# Conn_B.net
KiCad netlist of a schematic drawn in Altium Designer
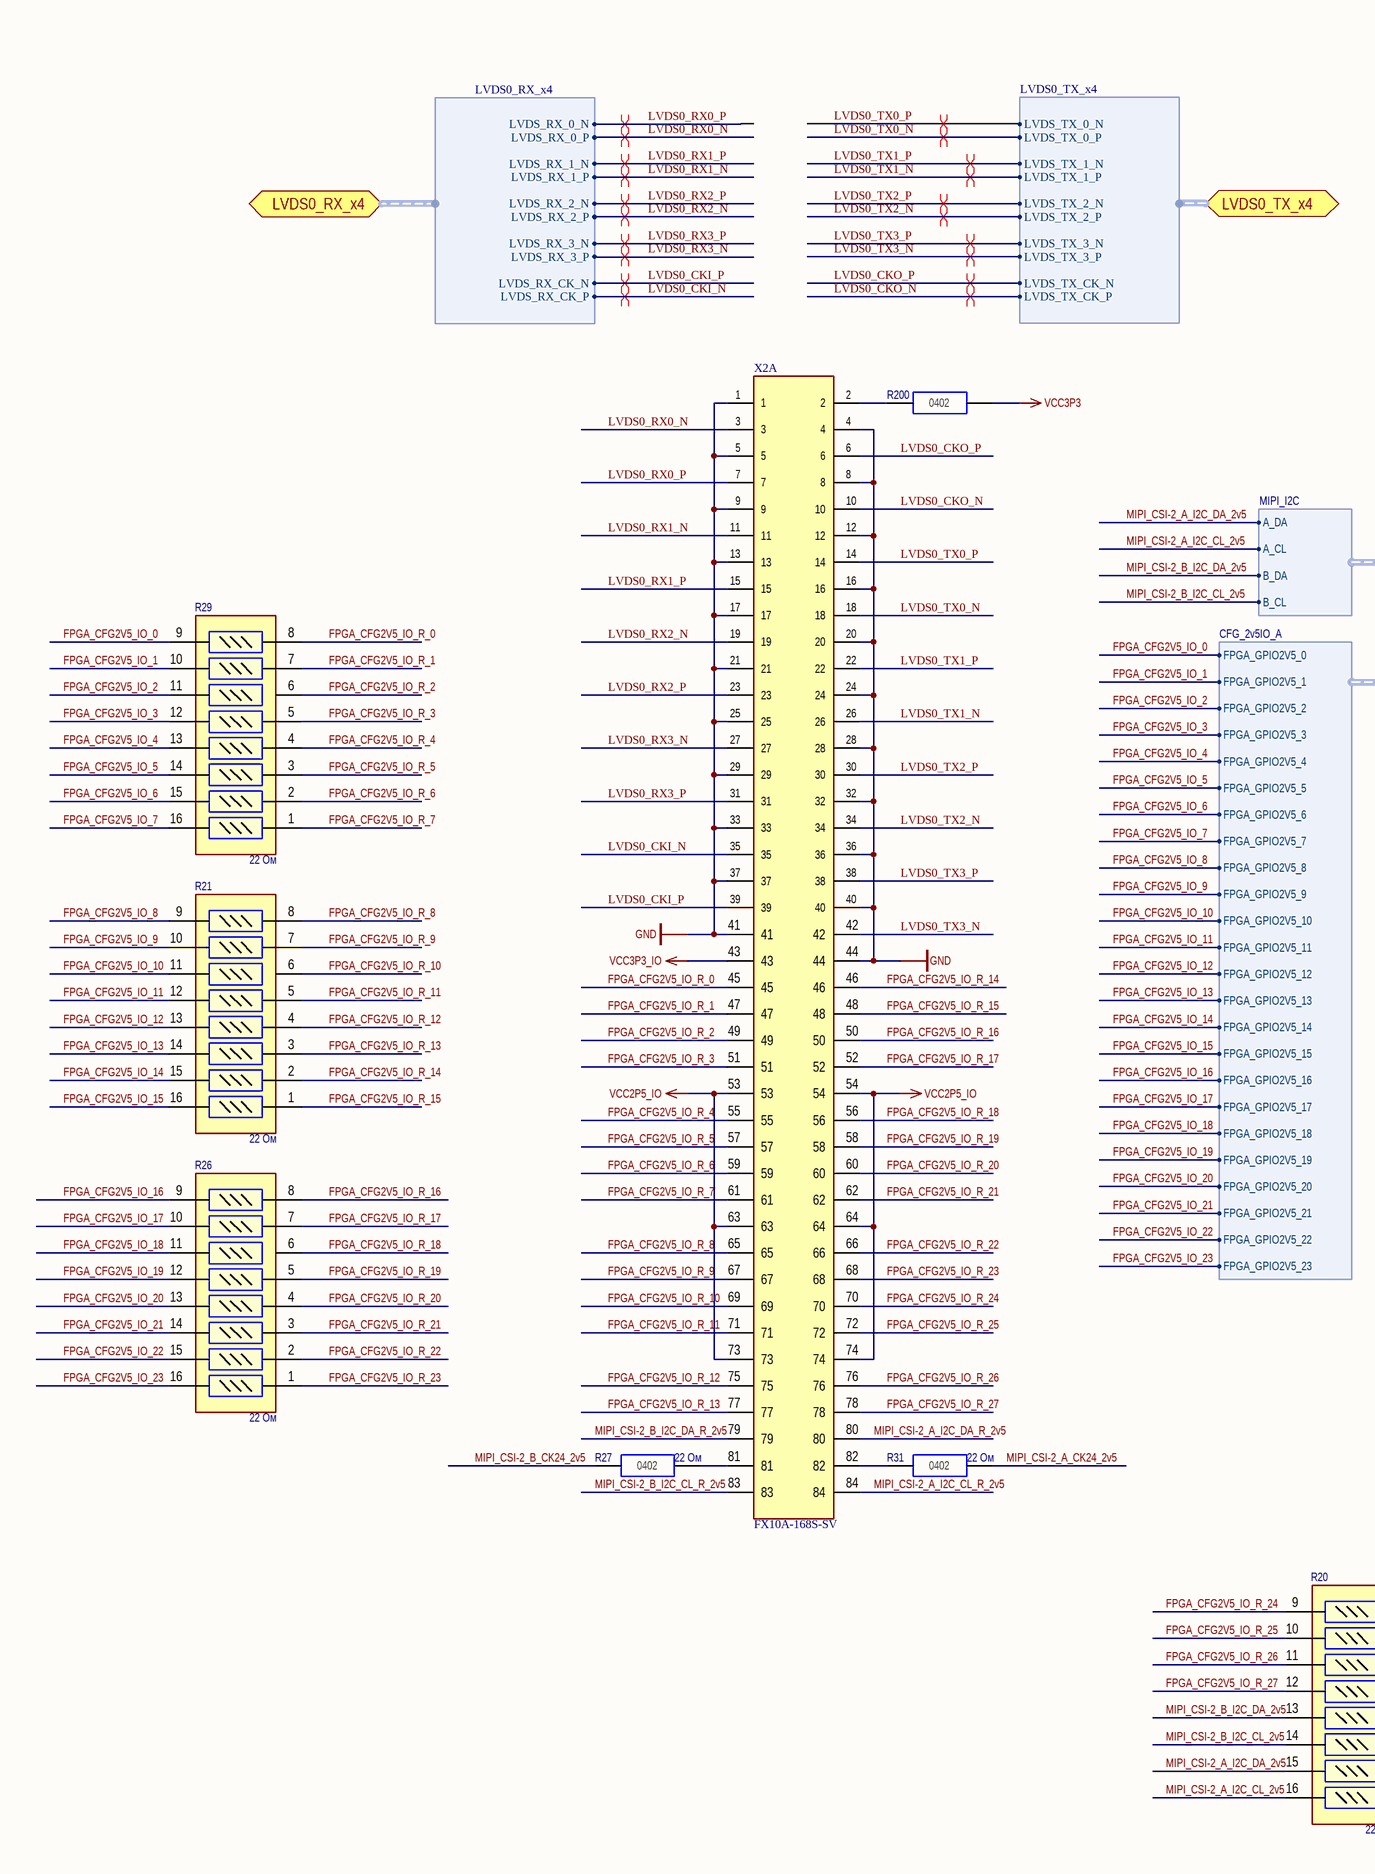
[diagram p0: Conn_B.SchDoc, left]
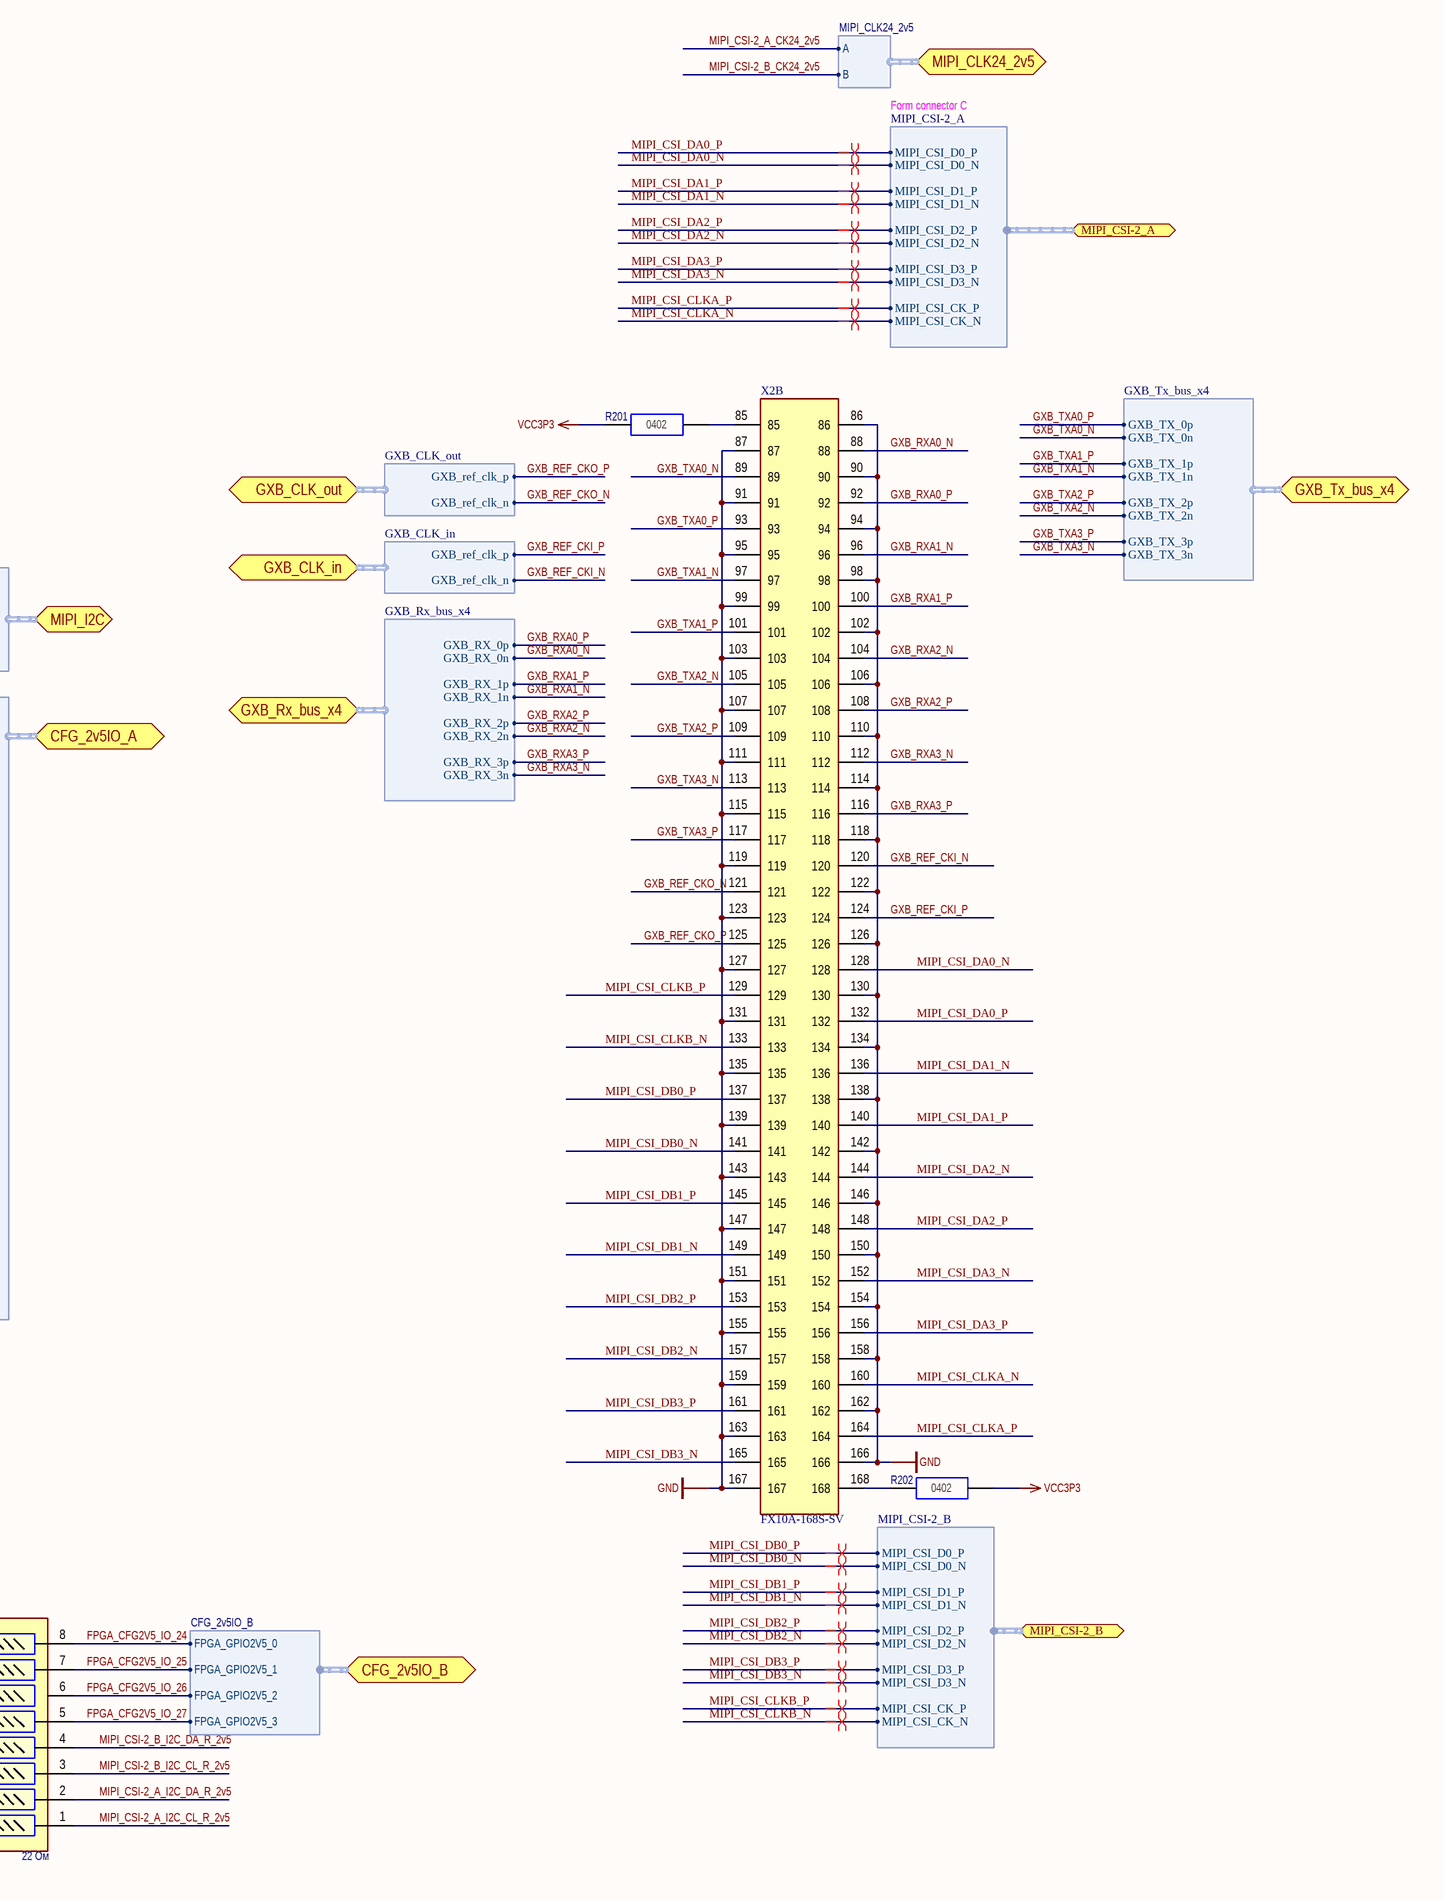
[diagram p1: Conn_B.SchDoc, right]

(export (version "E")
  (design (tool "Eeschema 10.0.6"))
  (components
    (comp (ref "R20")
      (value "22 Ом")
      (footprint "CAT16-J8")
      (description "Набор чип резисторов")
      (fields (field (name "Comment") "YC248-JR-07-22 Ом"))
      (libsource (lib "SD_IC") (part "YC248-JR-07-#"))
    )
    (comp (ref "R21")
      (value "22 Ом")
      (footprint "CAT16-J8")
      (description "Набор чип резисторов")
      (fields (field (name "Comment") "YC248-JR-07-22 Ом"))
      (libsource (lib "SD_IC") (part "YC248-JR-07-#"))
    )
    (comp (ref "R26")
      (value "22 Ом")
      (footprint "CAT16-J8")
      (description "Набор чип резисторов")
      (fields (field (name "Comment") "YC248-JR-07-22 Ом"))
      (libsource (lib "SD_IC") (part "YC248-JR-07-#"))
    )
    (comp (ref "R27")
      (value "22 Ом")
      (footprint "CR0402(1005)")
      (description "Чип резистор")
      (fields (field (name "TOLERANCE") "5%") (field (name "Comment") "CR0402-22 Ом-±5%"))
      (libsource (lib "Чип резисторы") (part "CR0402-#-±5%"))
    )
    (comp (ref "R29")
      (value "22 Ом")
      (footprint "CAT16-J8")
      (description "Набор чип резисторов")
      (fields (field (name "Comment") "YC248-JR-07-22 Ом"))
      (libsource (lib "SD_IC") (part "YC248-JR-07-#"))
    )
    (comp (ref "R31")
      (value "22 Ом")
      (footprint "CR0402(1005)")
      (description "Чип резистор")
      (fields (field (name "TOLERANCE") "5%") (field (name "Comment") "CR0402-22 Ом-±5%"))
      (libsource (lib "Чип резисторы") (part "CR0402-#-±5%"))
    )
    (comp (ref "R200")
      (value "CR0402-0 Ом-±5%")
      (footprint "CR0402(1005)")
      (description "Чип резистор")
      (fields (field (name "TOLERANCE") "5%"))
      (libsource (lib "Резисторы") (part "CR0402-#-±5%"))
    )
    (comp (ref "R201")
      (value "CR0402-0 Ом-±5%")
      (footprint "CR0402(1005)")
      (description "Чип резистор")
      (fields (field (name "TOLERANCE") "5%"))
      (libsource (lib "Резисторы") (part "CR0402-#-±5%"))
    )
    (comp (ref "R202")
      (value "CR0402-0 Ом-±5%")
      (footprint "CR0402(1005)")
      (description "Чип резистор")
      (fields (field (name "TOLERANCE") "5%"))
      (libsource (lib "Резисторы") (part "CR0402-#-±5%"))
    )
    (comp (ref "X2")
      (value "FX10A-168S-SV")
      (footprint "FX10A-168S-SV")
      (libsource (lib "SD_IC") (part "FX10A-168S-SV"))
    )
  )
  (nets
    (net (code "13") (name "/FPGA_CFG2V5_IO_0") (class "Default")
      (node (ref "R29") (pin "9") (pintype "passive"))
    )
    (net (code "14") (name "/FPGA_CFG2V5_IO_1") (class "Default")
      (node (ref "R29") (pin "10") (pintype "passive"))
    )
    (net (code "15") (name "/FPGA_CFG2V5_IO_2") (class "Default")
      (node (ref "R29") (pin "11") (pintype "passive"))
    )
    (net (code "16") (name "/FPGA_CFG2V5_IO_3") (class "Default")
      (node (ref "R29") (pin "12") (pintype "passive"))
    )
    (net (code "17") (name "/FPGA_CFG2V5_IO_4") (class "Default")
      (node (ref "R29") (pin "13") (pintype "passive"))
    )
    (net (code "18") (name "/FPGA_CFG2V5_IO_5") (class "Default")
      (node (ref "R29") (pin "14") (pintype "passive"))
    )
    (net (code "19") (name "/FPGA_CFG2V5_IO_6") (class "Default")
      (node (ref "R29") (pin "15") (pintype "passive"))
    )
    (net (code "20") (name "/FPGA_CFG2V5_IO_7") (class "Default")
      (node (ref "R29") (pin "16") (pintype "passive"))
    )
    (net (code "21") (name "/FPGA_CFG2V5_IO_8") (class "Default")
      (node (ref "R21") (pin "9") (pintype "passive"))
    )
    (net (code "22") (name "/FPGA_CFG2V5_IO_9") (class "Default")
      (node (ref "R21") (pin "10") (pintype "passive"))
    )
    (net (code "23") (name "/FPGA_CFG2V5_IO_10") (class "Default")
      (node (ref "R21") (pin "11") (pintype "passive"))
    )
    (net (code "24") (name "/FPGA_CFG2V5_IO_11") (class "Default")
      (node (ref "R21") (pin "12") (pintype "passive"))
    )
    (net (code "25") (name "/FPGA_CFG2V5_IO_12") (class "Default")
      (node (ref "R21") (pin "13") (pintype "passive"))
    )
    (net (code "26") (name "/FPGA_CFG2V5_IO_13") (class "Default")
      (node (ref "R21") (pin "14") (pintype "passive"))
    )
    (net (code "27") (name "/FPGA_CFG2V5_IO_14") (class "Default")
      (node (ref "R21") (pin "15") (pintype "passive"))
    )
    (net (code "28") (name "/FPGA_CFG2V5_IO_15") (class "Default")
      (node (ref "R21") (pin "16") (pintype "passive"))
    )
    (net (code "29") (name "/FPGA_CFG2V5_IO_16") (class "Default")
      (node (ref "R26") (pin "9") (pintype "passive"))
    )
    (net (code "30") (name "/FPGA_CFG2V5_IO_17") (class "Default")
      (node (ref "R26") (pin "10") (pintype "passive"))
    )
    (net (code "31") (name "/FPGA_CFG2V5_IO_18") (class "Default")
      (node (ref "R26") (pin "11") (pintype "passive"))
    )
    (net (code "32") (name "/FPGA_CFG2V5_IO_19") (class "Default")
      (node (ref "R26") (pin "12") (pintype "passive"))
    )
    (net (code "33") (name "/FPGA_CFG2V5_IO_20") (class "Default")
      (node (ref "R26") (pin "13") (pintype "passive"))
    )
    (net (code "34") (name "/FPGA_CFG2V5_IO_21") (class "Default")
      (node (ref "R26") (pin "14") (pintype "passive"))
    )
    (net (code "35") (name "/FPGA_CFG2V5_IO_22") (class "Default")
      (node (ref "R26") (pin "15") (pintype "passive"))
    )
    (net (code "36") (name "/FPGA_CFG2V5_IO_23") (class "Default")
      (node (ref "R26") (pin "16") (pintype "passive"))
    )
    (net (code "37") (name "/FPGA_CFG2V5_IO_24") (class "Default")
      (node (ref "R20") (pin "8") (pintype "passive"))
    )
    (net (code "38") (name "/FPGA_CFG2V5_IO_25") (class "Default")
      (node (ref "R20") (pin "7") (pintype "passive"))
    )
    (net (code "39") (name "/FPGA_CFG2V5_IO_26") (class "Default")
      (node (ref "R20") (pin "6") (pintype "passive"))
    )
    (net (code "40") (name "/FPGA_CFG2V5_IO_27") (class "Default")
      (node (ref "R20") (pin "5") (pintype "passive"))
    )
    (net (code "41") (name "/FPGA_CFG2V5_IO_R_0") (class "Default")
      (node (ref "R29") (pin "8") (pintype "passive"))
      (node (ref "X2") (pin "45") (pinfunction "45_45") (pintype "passive"))
    )
    (net (code "42") (name "/FPGA_CFG2V5_IO_R_1") (class "Default")
      (node (ref "R29") (pin "7") (pintype "passive"))
      (node (ref "X2") (pin "47") (pinfunction "47_47") (pintype "passive"))
    )
    (net (code "43") (name "/FPGA_CFG2V5_IO_R_2") (class "Default")
      (node (ref "R29") (pin "6") (pintype "passive"))
      (node (ref "X2") (pin "49") (pinfunction "49_49") (pintype "passive"))
    )
    (net (code "44") (name "/FPGA_CFG2V5_IO_R_3") (class "Default")
      (node (ref "R29") (pin "5") (pintype "passive"))
      (node (ref "X2") (pin "51") (pinfunction "51_51") (pintype "passive"))
    )
    (net (code "45") (name "/FPGA_CFG2V5_IO_R_4") (class "Default")
      (node (ref "R29") (pin "4") (pintype "passive"))
      (node (ref "X2") (pin "55") (pinfunction "55_55") (pintype "passive"))
    )
    (net (code "46") (name "/FPGA_CFG2V5_IO_R_5") (class "Default")
      (node (ref "R29") (pin "3") (pintype "passive"))
      (node (ref "X2") (pin "57") (pinfunction "57_57") (pintype "passive"))
    )
    (net (code "47") (name "/FPGA_CFG2V5_IO_R_6") (class "Default")
      (node (ref "R29") (pin "2") (pintype "passive"))
      (node (ref "X2") (pin "59") (pinfunction "59_59") (pintype "passive"))
    )
    (net (code "48") (name "/FPGA_CFG2V5_IO_R_7") (class "Default")
      (node (ref "R29") (pin "1") (pintype "passive"))
      (node (ref "X2") (pin "61") (pinfunction "61_61") (pintype "passive"))
    )
    (net (code "49") (name "/FPGA_CFG2V5_IO_R_8") (class "Default")
      (node (ref "R21") (pin "8") (pintype "passive"))
      (node (ref "X2") (pin "65") (pinfunction "65_65") (pintype "passive"))
    )
    (net (code "50") (name "/FPGA_CFG2V5_IO_R_9") (class "Default")
      (node (ref "R21") (pin "7") (pintype "passive"))
      (node (ref "X2") (pin "67") (pinfunction "67_67") (pintype "passive"))
    )
    (net (code "51") (name "/FPGA_CFG2V5_IO_R_10") (class "Default")
      (node (ref "R21") (pin "6") (pintype "passive"))
      (node (ref "X2") (pin "69") (pinfunction "69_69") (pintype "passive"))
    )
    (net (code "52") (name "/FPGA_CFG2V5_IO_R_11") (class "Default")
      (node (ref "R21") (pin "5") (pintype "passive"))
      (node (ref "X2") (pin "71") (pinfunction "71_71") (pintype "passive"))
    )
    (net (code "53") (name "/FPGA_CFG2V5_IO_R_12") (class "Default")
      (node (ref "R21") (pin "4") (pintype "passive"))
      (node (ref "X2") (pin "75") (pinfunction "75_75") (pintype "passive"))
    )
    (net (code "54") (name "/FPGA_CFG2V5_IO_R_13") (class "Default")
      (node (ref "R21") (pin "3") (pintype "passive"))
      (node (ref "X2") (pin "77") (pinfunction "77_77") (pintype "passive"))
    )
    (net (code "55") (name "/FPGA_CFG2V5_IO_R_14") (class "Default")
      (node (ref "R21") (pin "2") (pintype "passive"))
      (node (ref "X2") (pin "46") (pinfunction "46_46") (pintype "passive"))
    )
    (net (code "56") (name "/FPGA_CFG2V5_IO_R_15") (class "Default")
      (node (ref "R21") (pin "1") (pintype "passive"))
      (node (ref "X2") (pin "48") (pinfunction "48_48") (pintype "passive"))
    )
    (net (code "57") (name "/FPGA_CFG2V5_IO_R_16") (class "Default")
      (node (ref "R26") (pin "8") (pintype "passive"))
      (node (ref "X2") (pin "50") (pinfunction "50_50") (pintype "passive"))
    )
    (net (code "58") (name "/FPGA_CFG2V5_IO_R_17") (class "Default")
      (node (ref "R26") (pin "7") (pintype "passive"))
      (node (ref "X2") (pin "52") (pinfunction "52_52") (pintype "passive"))
    )
    (net (code "59") (name "/FPGA_CFG2V5_IO_R_18") (class "Default")
      (node (ref "R26") (pin "6") (pintype "passive"))
      (node (ref "X2") (pin "56") (pinfunction "56_56") (pintype "passive"))
    )
    (net (code "60") (name "/FPGA_CFG2V5_IO_R_19") (class "Default")
      (node (ref "R26") (pin "5") (pintype "passive"))
      (node (ref "X2") (pin "58") (pinfunction "58_58") (pintype "passive"))
    )
    (net (code "61") (name "/FPGA_CFG2V5_IO_R_20") (class "Default")
      (node (ref "R26") (pin "4") (pintype "passive"))
      (node (ref "X2") (pin "60") (pinfunction "60_60") (pintype "passive"))
    )
    (net (code "62") (name "/FPGA_CFG2V5_IO_R_21") (class "Default")
      (node (ref "R26") (pin "3") (pintype "passive"))
      (node (ref "X2") (pin "62") (pinfunction "62_62") (pintype "passive"))
    )
    (net (code "63") (name "/FPGA_CFG2V5_IO_R_22") (class "Default")
      (node (ref "R26") (pin "2") (pintype "passive"))
      (node (ref "X2") (pin "66") (pinfunction "66_66") (pintype "passive"))
    )
    (net (code "64") (name "/FPGA_CFG2V5_IO_R_23") (class "Default")
      (node (ref "R26") (pin "1") (pintype "passive"))
      (node (ref "X2") (pin "68") (pinfunction "68_68") (pintype "passive"))
    )
    (net (code "65") (name "/FPGA_CFG2V5_IO_R_24") (class "Default")
      (node (ref "R20") (pin "9") (pintype "passive"))
      (node (ref "X2") (pin "70") (pinfunction "70_70") (pintype "passive"))
    )
    (net (code "66") (name "/FPGA_CFG2V5_IO_R_25") (class "Default")
      (node (ref "R20") (pin "10") (pintype "passive"))
      (node (ref "X2") (pin "72") (pinfunction "72_72") (pintype "passive"))
    )
    (net (code "67") (name "/FPGA_CFG2V5_IO_R_26") (class "Default")
      (node (ref "R20") (pin "11") (pintype "passive"))
      (node (ref "X2") (pin "76") (pinfunction "76_76") (pintype "passive"))
    )
    (net (code "68") (name "/FPGA_CFG2V5_IO_R_27") (class "Default")
      (node (ref "R20") (pin "12") (pintype "passive"))
      (node (ref "X2") (pin "78") (pinfunction "78_78") (pintype "passive"))
    )
    (net (code "69") (name "/GXB_REF_CKI_N") (class "Default")
      (node (ref "X2") (pin "120") (pinfunction "120_120") (pintype "passive"))
    )
    (net (code "70") (name "/GXB_REF_CKI_P") (class "Default")
      (node (ref "X2") (pin "124") (pinfunction "124_124") (pintype "passive"))
    )
    (net (code "71") (name "/GXB_REF_CKO_N") (class "Default")
      (node (ref "X2") (pin "121") (pinfunction "121_121") (pintype "passive"))
    )
    (net (code "72") (name "/GXB_REF_CKO_P") (class "Default")
      (node (ref "X2") (pin "125") (pinfunction "125_125") (pintype "passive"))
    )
    (net (code "73") (name "/GXB_RXA0_N") (class "Default")
      (node (ref "X2") (pin "88") (pinfunction "88_88") (pintype "passive"))
    )
    (net (code "74") (name "/GXB_RXA0_P") (class "Default")
      (node (ref "X2") (pin "92") (pinfunction "92_92") (pintype "passive"))
    )
    (net (code "75") (name "/GXB_RXA1_N") (class "Default")
      (node (ref "X2") (pin "96") (pinfunction "96_96") (pintype "passive"))
    )
    (net (code "76") (name "/GXB_RXA1_P") (class "Default")
      (node (ref "X2") (pin "100") (pinfunction "100_100") (pintype "passive"))
    )
    (net (code "77") (name "/GXB_RXA2_N") (class "Default")
      (node (ref "X2") (pin "104") (pinfunction "104_104") (pintype "passive"))
    )
    (net (code "78") (name "/GXB_RXA2_P") (class "Default")
      (node (ref "X2") (pin "108") (pinfunction "108_108") (pintype "passive"))
    )
    (net (code "79") (name "/GXB_RXA3_N") (class "Default")
      (node (ref "X2") (pin "112") (pinfunction "112_112") (pintype "passive"))
    )
    (net (code "80") (name "/GXB_RXA3_P") (class "Default")
      (node (ref "X2") (pin "116") (pinfunction "116_116") (pintype "passive"))
    )
    (net (code "81") (name "/GXB_TXA0_N") (class "Default")
      (node (ref "X2") (pin "89") (pinfunction "89_89") (pintype "passive"))
    )
    (net (code "82") (name "/GXB_TXA0_P") (class "Default")
      (node (ref "X2") (pin "93") (pinfunction "93_93") (pintype "passive"))
    )
    (net (code "83") (name "/GXB_TXA1_N") (class "Default")
      (node (ref "X2") (pin "97") (pinfunction "97_97") (pintype "passive"))
    )
    (net (code "84") (name "/GXB_TXA1_P") (class "Default")
      (node (ref "X2") (pin "101") (pinfunction "101_101") (pintype "passive"))
    )
    (net (code "85") (name "/GXB_TXA2_N") (class "Default")
      (node (ref "X2") (pin "105") (pinfunction "105_105") (pintype "passive"))
    )
    (net (code "86") (name "/GXB_TXA2_P") (class "Default")
      (node (ref "X2") (pin "109") (pinfunction "109_109") (pintype "passive"))
    )
    (net (code "87") (name "/GXB_TXA3_N") (class "Default")
      (node (ref "X2") (pin "113") (pinfunction "113_113") (pintype "passive"))
    )
    (net (code "88") (name "/GXB_TXA3_P") (class "Default")
      (node (ref "X2") (pin "117") (pinfunction "117_117") (pintype "passive"))
    )
    (net (code "89") (name "/LVDS0_CKI_N") (class "Default")
      (node (ref "X2") (pin "35") (pinfunction "35_35") (pintype "passive"))
    )
    (net (code "90") (name "/LVDS0_CKI_P") (class "Default")
      (node (ref "X2") (pin "39") (pinfunction "39_39") (pintype "passive"))
    )
    (net (code "91") (name "/LVDS0_CKO_N") (class "Default")
      (node (ref "X2") (pin "10") (pinfunction "10_10") (pintype "passive"))
    )
    (net (code "92") (name "/LVDS0_CKO_P") (class "Default")
      (node (ref "X2") (pin "6") (pinfunction "6_6") (pintype "passive"))
    )
    (net (code "93") (name "/LVDS0_RX0_N") (class "Default")
      (node (ref "X2") (pin "3") (pinfunction "3_3") (pintype "passive"))
    )
    (net (code "94") (name "/LVDS0_RX0_P") (class "Default")
      (node (ref "X2") (pin "7") (pinfunction "7_7") (pintype "passive"))
    )
    (net (code "95") (name "/LVDS0_RX1_N") (class "Default")
      (node (ref "X2") (pin "11") (pinfunction "11_11") (pintype "passive"))
    )
    (net (code "96") (name "/LVDS0_RX1_P") (class "Default")
      (node (ref "X2") (pin "15") (pinfunction "15_15") (pintype "passive"))
    )
    (net (code "97") (name "/LVDS0_RX2_N") (class "Default")
      (node (ref "X2") (pin "19") (pinfunction "19_19") (pintype "passive"))
    )
    (net (code "98") (name "/LVDS0_RX2_P") (class "Default")
      (node (ref "X2") (pin "23") (pinfunction "23_23") (pintype "passive"))
    )
    (net (code "99") (name "/LVDS0_RX3_N") (class "Default")
      (node (ref "X2") (pin "27") (pinfunction "27_27") (pintype "passive"))
    )
    (net (code "100") (name "/LVDS0_RX3_P") (class "Default")
      (node (ref "X2") (pin "31") (pinfunction "31_31") (pintype "passive"))
    )
    (net (code "101") (name "/LVDS0_TX0_N") (class "Default")
      (node (ref "X2") (pin "18") (pinfunction "18_18") (pintype "passive"))
    )
    (net (code "102") (name "/LVDS0_TX0_P") (class "Default")
      (node (ref "X2") (pin "14") (pinfunction "14_14") (pintype "passive"))
    )
    (net (code "103") (name "/LVDS0_TX1_N") (class "Default")
      (node (ref "X2") (pin "26") (pinfunction "26_26") (pintype "passive"))
    )
    (net (code "104") (name "/LVDS0_TX1_P") (class "Default")
      (node (ref "X2") (pin "22") (pinfunction "22_22") (pintype "passive"))
    )
    (net (code "105") (name "/LVDS0_TX2_N") (class "Default")
      (node (ref "X2") (pin "34") (pinfunction "34_34") (pintype "passive"))
    )
    (net (code "106") (name "/LVDS0_TX2_P") (class "Default")
      (node (ref "X2") (pin "30") (pinfunction "30_30") (pintype "passive"))
    )
    (net (code "107") (name "/LVDS0_TX3_N") (class "Default")
      (node (ref "X2") (pin "42") (pinfunction "42_42") (pintype "passive"))
    )
    (net (code "108") (name "/LVDS0_TX3_P") (class "Default")
      (node (ref "X2") (pin "38") (pinfunction "38_38") (pintype "passive"))
    )
    (net (code "109") (name "/MIPI_CSI-2_A_CK24_2v5") (class "Default")
      (node (ref "R31") (pin "2") (pinfunction "-_2") (pintype "passive"))
    )
    (net (code "110") (name "/MIPI_CSI-2_A_I2C_CL_2v5") (class "Default")
      (node (ref "R20") (pin "16") (pintype "passive"))
    )
    (net (code "111") (name "/MIPI_CSI-2_A_I2C_CL_R_2v5") (class "Default")
      (node (ref "R20") (pin "1") (pintype "passive"))
      (node (ref "X2") (pin "84") (pinfunction "84_84") (pintype "passive"))
    )
    (net (code "112") (name "/MIPI_CSI-2_A_I2C_DA_2v5") (class "Default")
      (node (ref "R20") (pin "15") (pintype "passive"))
    )
    (net (code "113") (name "/MIPI_CSI-2_A_I2C_DA_R_2v5") (class "Default")
      (node (ref "R20") (pin "2") (pintype "passive"))
      (node (ref "X2") (pin "80") (pinfunction "80_80") (pintype "passive"))
    )
    (net (code "114") (name "/MIPI_CSI-2_B_CK24_2v5") (class "Default")
      (node (ref "R27") (pin "1") (pinfunction "+_1") (pintype "passive"))
    )
    (net (code "115") (name "/MIPI_CSI-2_B_I2C_CL_2v5") (class "Default")
      (node (ref "R20") (pin "14") (pintype "passive"))
    )
    (net (code "116") (name "/MIPI_CSI-2_B_I2C_CL_R_2v5") (class "Default")
      (node (ref "R20") (pin "3") (pintype "passive"))
      (node (ref "X2") (pin "83") (pinfunction "83_83") (pintype "passive"))
    )
    (net (code "117") (name "/MIPI_CSI-2_B_I2C_DA_2v5") (class "Default")
      (node (ref "R20") (pin "13") (pintype "passive"))
    )
    (net (code "118") (name "/MIPI_CSI-2_B_I2C_DA_R_2v5") (class "Default")
      (node (ref "R20") (pin "4") (pintype "passive"))
      (node (ref "X2") (pin "79") (pinfunction "79_79") (pintype "passive"))
    )
    (net (code "119") (name "/MIPI_CSI_CLKA_N") (class "Default")
      (node (ref "X2") (pin "160") (pinfunction "160_160") (pintype "passive"))
    )
    (net (code "120") (name "/MIPI_CSI_CLKA_P") (class "Default")
      (node (ref "X2") (pin "164") (pinfunction "164_164") (pintype "passive"))
    )
    (net (code "121") (name "/MIPI_CSI_CLKB_N") (class "Default")
      (node (ref "X2") (pin "133") (pinfunction "133_133") (pintype "passive"))
    )
    (net (code "122") (name "/MIPI_CSI_CLKB_P") (class "Default")
      (node (ref "X2") (pin "129") (pinfunction "129_129") (pintype "passive"))
    )
    (net (code "123") (name "/MIPI_CSI_DA0_N") (class "Default")
      (node (ref "X2") (pin "128") (pinfunction "128_128") (pintype "passive"))
    )
    (net (code "124") (name "/MIPI_CSI_DA0_P") (class "Default")
      (node (ref "X2") (pin "132") (pinfunction "132_132") (pintype "passive"))
    )
    (net (code "125") (name "/MIPI_CSI_DA1_N") (class "Default")
      (node (ref "X2") (pin "136") (pinfunction "136_136") (pintype "passive"))
    )
    (net (code "126") (name "/MIPI_CSI_DA1_P") (class "Default")
      (node (ref "X2") (pin "140") (pinfunction "140_140") (pintype "passive"))
    )
    (net (code "127") (name "/MIPI_CSI_DA2_N") (class "Default")
      (node (ref "X2") (pin "144") (pinfunction "144_144") (pintype "passive"))
    )
    (net (code "128") (name "/MIPI_CSI_DA2_P") (class "Default")
      (node (ref "X2") (pin "148") (pinfunction "148_148") (pintype "passive"))
    )
    (net (code "129") (name "/MIPI_CSI_DA3_N") (class "Default")
      (node (ref "X2") (pin "152") (pinfunction "152_152") (pintype "passive"))
    )
    (net (code "130") (name "/MIPI_CSI_DA3_P") (class "Default")
      (node (ref "X2") (pin "156") (pinfunction "156_156") (pintype "passive"))
    )
    (net (code "131") (name "/MIPI_CSI_DB0_N") (class "Default")
      (node (ref "X2") (pin "141") (pinfunction "141_141") (pintype "passive"))
    )
    (net (code "132") (name "/MIPI_CSI_DB0_P") (class "Default")
      (node (ref "X2") (pin "137") (pinfunction "137_137") (pintype "passive"))
    )
    (net (code "133") (name "/MIPI_CSI_DB1_N") (class "Default")
      (node (ref "X2") (pin "149") (pinfunction "149_149") (pintype "passive"))
    )
    (net (code "134") (name "/MIPI_CSI_DB1_P") (class "Default")
      (node (ref "X2") (pin "145") (pinfunction "145_145") (pintype "passive"))
    )
    (net (code "135") (name "/MIPI_CSI_DB2_N") (class "Default")
      (node (ref "X2") (pin "157") (pinfunction "157_157") (pintype "passive"))
    )
    (net (code "136") (name "/MIPI_CSI_DB2_P") (class "Default")
      (node (ref "X2") (pin "153") (pinfunction "153_153") (pintype "passive"))
    )
    (net (code "137") (name "/MIPI_CSI_DB3_N") (class "Default")
      (node (ref "X2") (pin "165") (pinfunction "165_165") (pintype "passive"))
    )
    (net (code "138") (name "/MIPI_CSI_DB3_P") (class "Default")
      (node (ref "X2") (pin "161") (pinfunction "161_161") (pintype "passive"))
    )
    (net (code "151") (name "GND") (class "Default")
      (node (ref "X2") (pin "1") (pinfunction "1_1") (pintype "passive"))
      (node (ref "X2") (pin "102") (pinfunction "102_102") (pintype "passive"))
      (node (ref "X2") (pin "103") (pinfunction "103_103") (pintype "passive"))
      (node (ref "X2") (pin "106") (pinfunction "106_106") (pintype "passive"))
      (node (ref "X2") (pin "107") (pinfunction "107_107") (pintype "passive"))
      (node (ref "X2") (pin "110") (pinfunction "110_110") (pintype "passive"))
      (node (ref "X2") (pin "111") (pinfunction "111_111") (pintype "passive"))
      (node (ref "X2") (pin "114") (pinfunction "114_114") (pintype "passive"))
      (node (ref "X2") (pin "115") (pinfunction "115_115") (pintype "passive"))
      (node (ref "X2") (pin "118") (pinfunction "118_118") (pintype "passive"))
      (node (ref "X2") (pin "119") (pinfunction "119_119") (pintype "passive"))
      (node (ref "X2") (pin "12") (pinfunction "12_12") (pintype "passive"))
      (node (ref "X2") (pin "122") (pinfunction "122_122") (pintype "passive"))
      (node (ref "X2") (pin "123") (pinfunction "123_123") (pintype "passive"))
      (node (ref "X2") (pin "126") (pinfunction "126_126") (pintype "passive"))
      (node (ref "X2") (pin "127") (pinfunction "127_127") (pintype "passive"))
      (node (ref "X2") (pin "13") (pinfunction "13_13") (pintype "passive"))
      (node (ref "X2") (pin "130") (pinfunction "130_130") (pintype "passive"))
      (node (ref "X2") (pin "131") (pinfunction "131_131") (pintype "passive"))
      (node (ref "X2") (pin "134") (pinfunction "134_134") (pintype "passive"))
      (node (ref "X2") (pin "135") (pinfunction "135_135") (pintype "passive"))
      (node (ref "X2") (pin "138") (pinfunction "138_138") (pintype "passive"))
      (node (ref "X2") (pin "139") (pinfunction "139_139") (pintype "passive"))
      (node (ref "X2") (pin "142") (pinfunction "142_142") (pintype "passive"))
      (node (ref "X2") (pin "143") (pinfunction "143_143") (pintype "passive"))
      (node (ref "X2") (pin "146") (pinfunction "146_146") (pintype "passive"))
      (node (ref "X2") (pin "147") (pinfunction "147_147") (pintype "passive"))
      (node (ref "X2") (pin "150") (pinfunction "150_150") (pintype "passive"))
      (node (ref "X2") (pin "151") (pinfunction "151_151") (pintype "passive"))
      (node (ref "X2") (pin "154") (pinfunction "154_154") (pintype "passive"))
      (node (ref "X2") (pin "155") (pinfunction "155_155") (pintype "passive"))
      (node (ref "X2") (pin "158") (pinfunction "158_158") (pintype "passive"))
      (node (ref "X2") (pin "159") (pinfunction "159_159") (pintype "passive"))
      (node (ref "X2") (pin "16") (pinfunction "16_16") (pintype "passive"))
      (node (ref "X2") (pin "162") (pinfunction "162_162") (pintype "passive"))
      (node (ref "X2") (pin "163") (pinfunction "163_163") (pintype "passive"))
      (node (ref "X2") (pin "166") (pinfunction "166_166") (pintype "passive"))
      (node (ref "X2") (pin "167") (pinfunction "167_167") (pintype "passive"))
      (node (ref "X2") (pin "17") (pinfunction "17_17") (pintype "passive"))
      (node (ref "X2") (pin "20") (pinfunction "20_20") (pintype "passive"))
      (node (ref "X2") (pin "21") (pinfunction "21_21") (pintype "passive"))
      (node (ref "X2") (pin "24") (pinfunction "24_24") (pintype "passive"))
      (node (ref "X2") (pin "25") (pinfunction "25_25") (pintype "passive"))
      (node (ref "X2") (pin "28") (pinfunction "28_28") (pintype "passive"))
      (node (ref "X2") (pin "29") (pinfunction "29_29") (pintype "passive"))
      (node (ref "X2") (pin "32") (pinfunction "32_32") (pintype "passive"))
      (node (ref "X2") (pin "33") (pinfunction "33_33") (pintype "passive"))
      (node (ref "X2") (pin "36") (pinfunction "36_36") (pintype "passive"))
      (node (ref "X2") (pin "37") (pinfunction "37_37") (pintype "passive"))
      (node (ref "X2") (pin "4") (pinfunction "4_4") (pintype "passive"))
      (node (ref "X2") (pin "40") (pinfunction "40_40") (pintype "passive"))
      (node (ref "X2") (pin "41") (pinfunction "41_41") (pintype "passive"))
      (node (ref "X2") (pin "44") (pinfunction "44_44") (pintype "passive"))
      (node (ref "X2") (pin "5") (pinfunction "5_5") (pintype "passive"))
      (node (ref "X2") (pin "8") (pinfunction "8_8") (pintype "passive"))
      (node (ref "X2") (pin "86") (pinfunction "86_86") (pintype "passive"))
      (node (ref "X2") (pin "87") (pinfunction "87_87") (pintype "passive"))
      (node (ref "X2") (pin "9") (pinfunction "9_9") (pintype "passive"))
      (node (ref "X2") (pin "90") (pinfunction "90_90") (pintype "passive"))
      (node (ref "X2") (pin "91") (pinfunction "91_91") (pintype "passive"))
      (node (ref "X2") (pin "94") (pinfunction "94_94") (pintype "passive"))
      (node (ref "X2") (pin "95") (pinfunction "95_95") (pintype "passive"))
      (node (ref "X2") (pin "98") (pinfunction "98_98") (pintype "passive"))
      (node (ref "X2") (pin "99") (pinfunction "99_99") (pintype "passive"))
    )
    (net (code "152") (name "Net-(R27--)") (class "Default")
      (node (ref "R27") (pin "2") (pinfunction "-_2") (pintype "passive"))
      (node (ref "X2") (pin "81") (pinfunction "81_81") (pintype "passive"))
    )
    (net (code "153") (name "Net-(R31-+)") (class "Default")
      (node (ref "R31") (pin "1") (pinfunction "+_1") (pintype "passive"))
      (node (ref "X2") (pin "82") (pinfunction "82_82") (pintype "passive"))
    )
    (net (code "154") (name "Net-(R200-+)") (class "Default")
      (node (ref "R200") (pin "1") (pinfunction "+_1") (pintype "passive"))
      (node (ref "X2") (pin "2") (pinfunction "2_2") (pintype "passive"))
    )
    (net (code "155") (name "Net-(R201--)") (class "Default")
      (node (ref "R201") (pin "2") (pinfunction "-_2") (pintype "passive"))
      (node (ref "X2") (pin "85") (pinfunction "85_85") (pintype "passive"))
    )
    (net (code "156") (name "Net-(R202-+)") (class "Default")
      (node (ref "R202") (pin "1") (pinfunction "+_1") (pintype "passive"))
      (node (ref "X2") (pin "168") (pinfunction "168_168") (pintype "passive"))
    )
    (net (code "157") (name "VCC2P5_IO") (class "Default")
      (node (ref "X2") (pin "53") (pinfunction "53_53") (pintype "passive"))
      (node (ref "X2") (pin "54") (pinfunction "54_54") (pintype "passive"))
      (node (ref "X2") (pin "63") (pinfunction "63_63") (pintype "passive"))
      (node (ref "X2") (pin "64") (pinfunction "64_64") (pintype "passive"))
      (node (ref "X2") (pin "73") (pinfunction "73_73") (pintype "passive"))
      (node (ref "X2") (pin "74") (pinfunction "74_74") (pintype "passive"))
    )
    (net (code "158") (name "VCC3P3") (class "Default")
      (node (ref "R200") (pin "2") (pinfunction "-_2") (pintype "passive"))
      (node (ref "R201") (pin "1") (pinfunction "+_1") (pintype "passive"))
      (node (ref "R202") (pin "2") (pinfunction "-_2") (pintype "passive"))
    )
    (net (code "159") (name "VCC3P3_IO") (class "Default")
      (node (ref "X2") (pin "43") (pinfunction "43_43") (pintype "passive"))
    )
  )
)
